# peripherals.net
KiCad netlist of a schematic drawn in Altium Designer
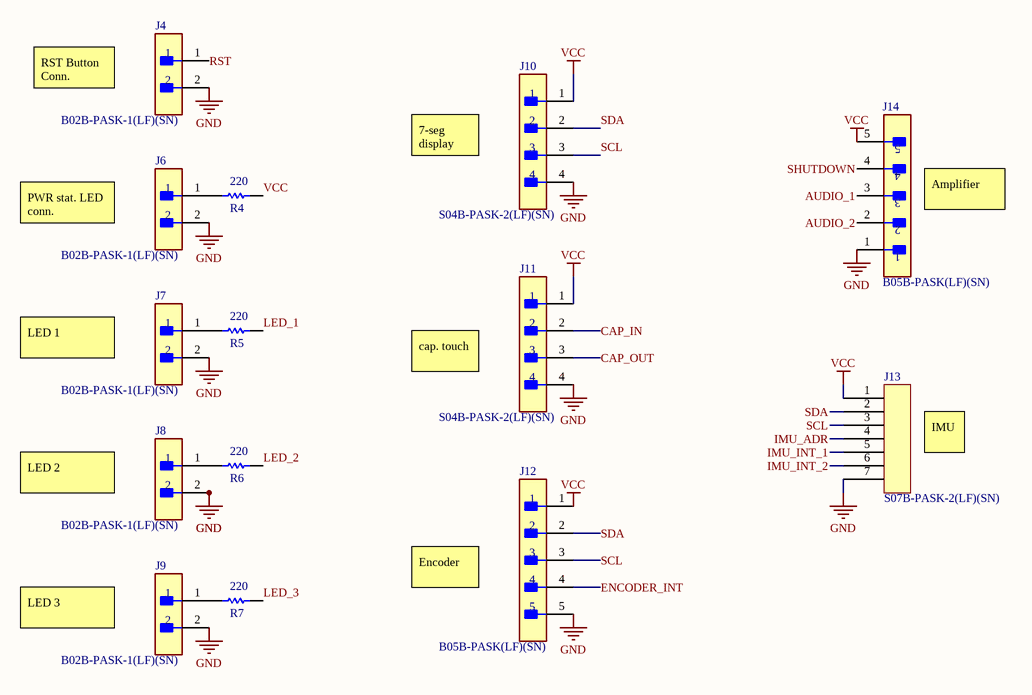
[diagram p0: peripherals.SchDoc]

(export (version "E")
  (design (tool "Eeschema 10.0.6"))
  (components
    (comp (ref "J4")
      (value "B02B-PASK-1(LF)(SN)")
      (footprint "FP-B02B-PASK-1_LF_SN-MFG")
      (description "CONN HEADER VERT 2POS 2MM")
      (libsource (lib "Altium Content Vault") (part "3bc925449376181038e59eaffc5286c"))
    )
    (comp (ref "J6")
      (value "B02B-PASK-1(LF)(SN)")
      (footprint "FP-B02B-PASK-1_LF_SN-MFG")
      (description "CONN HEADER VERT 2POS 2MM")
      (libsource (lib "Altium Content Vault") (part "3bc925449376181038e59eaffc5286c"))
    )
    (comp (ref "J7")
      (value "B02B-PASK-1(LF)(SN)")
      (footprint "FP-B02B-PASK-1_LF_SN-MFG")
      (description "CONN HEADER VERT 2POS 2MM")
      (libsource (lib "Altium Content Vault") (part "3bc925449376181038e59eaffc5286c"))
    )
    (comp (ref "J8")
      (value "B02B-PASK-1(LF)(SN)")
      (footprint "FP-B02B-PASK-1_LF_SN-MFG")
      (description "CONN HEADER VERT 2POS 2MM")
      (libsource (lib "Altium Content Vault") (part "3bc925449376181038e59eaffc5286c"))
    )
    (comp (ref "J9")
      (value "B02B-PASK-1(LF)(SN)")
      (footprint "FP-B02B-PASK-1_LF_SN-MFG")
      (description "CONN HEADER VERT 2POS 2MM")
      (libsource (lib "Altium Content Vault") (part "3bc925449376181038e59eaffc5286c"))
    )
    (comp (ref "J10")
      (value "S04B-PASK-2(LF)(SN)")
      (footprint "FP-S04B-PASK-2_LF_SN-MFG")
      (description "CONN HEADER R/A 4POS 2MM")
      (libsource (lib "Altium Content Vault") (part "299a8cea1bdcbc3624fe62c390fa72c"))
    )
    (comp (ref "J11")
      (value "S04B-PASK-2(LF)(SN)")
      (footprint "FP-S04B-PASK-2_LF_SN-MFG")
      (description "CONN HEADER R/A 4POS 2MM")
      (libsource (lib "Altium Content Vault") (part "299a8cea1bdcbc3624fe62c390fa72c"))
    )
    (comp (ref "J12")
      (value "B05B-PASK(LF)(SN)")
      (footprint "FP-B05B-PASK_LF_SN-MFG")
      (description "CONN HEADER VERT 5POS 2MM")
      (libsource (lib "Altium Content Vault") (part "bf93c07fd2649a848d0ec8585582aab"))
    )
    (comp (ref "J13")
      (value "S07B-PASK-2(LF)(SN)")
      (footprint "S07B-PASK-2(LF)(SN)-Footprint-1")
      (description "Conn Shrouded Header HDR 7 POS 2mm Solder RA Thru-Hole Box")
      (libsource (lib "University of Pittsburgh") (part "S07B-PASK-2(LF)(SN)-Symbol-1"))
    )
    (comp (ref "J14")
      (value "B05B-PASK(LF)(SN)")
      (footprint "FP-B05B-PASK_LF_SN-MFG")
      (description "CONN HEADER VERT 5POS 2MM")
      (libsource (lib "") (part "bf93c07fd2649a848d0ec8585582aab_1"))
    )
    (comp (ref "R4")
      (value "220")
      (footprint "RESA60-630X240")
      (description "RES 1K OHM 1/4W 1% AXIAL")
      (fields (field (name "TOLERANCE") "1%"))
      (libsource (lib "University of Pittsburgh") (part "RES-2"))
    )
    (comp (ref "R5")
      (value "220")
      (footprint "RESA60-630X240")
      (description "RES 1K OHM 1/4W 1% AXIAL")
      (fields (field (name "TOLERANCE") "1%"))
      (libsource (lib "University of Pittsburgh") (part "RES-2"))
    )
    (comp (ref "R6")
      (value "220")
      (footprint "RESA60-630X240")
      (description "RES 1K OHM 1/4W 1% AXIAL")
      (fields (field (name "TOLERANCE") "1%"))
      (libsource (lib "University of Pittsburgh") (part "RES-2"))
    )
    (comp (ref "R7")
      (value "220")
      (footprint "RESA60-630X240")
      (description "RES 1K OHM 1/4W 1% AXIAL")
      (fields (field (name "TOLERANCE") "1%"))
      (libsource (lib "University of Pittsburgh") (part "RES-2"))
    )
  )
  (nets
    (net (code "1") (name "/AUDIO_1") (class "Default")
      (node (ref "J14") (pin "3") (pinfunction "3_3") (pintype "passive"))
    )
    (net (code "2") (name "/AUDIO_2") (class "Default")
      (node (ref "J14") (pin "2") (pinfunction "2_2") (pintype "passive"))
    )
    (net (code "3") (name "/CAP_IN") (class "Default")
      (node (ref "J11") (pin "2") (pinfunction "2_2") (pintype "passive"))
    )
    (net (code "4") (name "/CAP_OUT") (class "Default")
      (node (ref "J11") (pin "3") (pinfunction "3_3") (pintype "passive"))
    )
    (net (code "5") (name "/ENCODER_INT") (class "Default")
      (node (ref "J12") (pin "4") (pinfunction "4_4") (pintype "passive"))
    )
    (net (code "6") (name "/IMU_ADR") (class "Default") (node (ref "J13") (pin "4") (pintype "passive")))
    (net (code "7") (name "/IMU_INT_1") (class "Default") (node (ref "J13") (pin "5") (pintype "passive")))
    (net (code "8") (name "/IMU_INT_2") (class "Default") (node (ref "J13") (pin "6") (pintype "passive")))
    (net (code "9") (name "/LED_1") (class "Default")
      (node (ref "R5") (pin "2") (pinfunction "2_2") (pintype "passive"))
    )
    (net (code "10") (name "/LED_2") (class "Default")
      (node (ref "R6") (pin "2") (pinfunction "2_2") (pintype "passive"))
    )
    (net (code "11") (name "/LED_3") (class "Default")
      (node (ref "R7") (pin "2") (pinfunction "2_2") (pintype "passive"))
    )
    (net (code "12") (name "/RST") (class "Default")
      (node (ref "J4") (pin "1") (pinfunction "1_1") (pintype "passive"))
    )
    (net (code "13") (name "/SCL") (class "Default")
      (node (ref "J10") (pin "3") (pinfunction "3_3") (pintype "passive"))
      (node (ref "J12") (pin "3") (pinfunction "3_3") (pintype "passive"))
      (node (ref "J13") (pin "3") (pintype "passive"))
    )
    (net (code "14") (name "/SDA") (class "Default")
      (node (ref "J10") (pin "2") (pinfunction "2_2") (pintype "passive"))
      (node (ref "J12") (pin "2") (pinfunction "2_2") (pintype "passive"))
      (node (ref "J13") (pin "2") (pintype "passive"))
    )
    (net (code "15") (name "/SHUTDOWN") (class "Default")
      (node (ref "J14") (pin "4") (pinfunction "4_4") (pintype "passive"))
    )
    (net (code "16") (name "GND") (class "Default")
      (node (ref "J10") (pin "4") (pinfunction "4_4") (pintype "passive"))
      (node (ref "J11") (pin "4") (pinfunction "4_4") (pintype "passive"))
      (node (ref "J12") (pin "5") (pinfunction "5_5") (pintype "passive"))
      (node (ref "J13") (pin "7") (pintype "passive"))
      (node (ref "J14") (pin "1") (pinfunction "1_1") (pintype "passive"))
      (node (ref "J4") (pin "2") (pinfunction "2_2") (pintype "passive"))
      (node (ref "J6") (pin "2") (pinfunction "2_2") (pintype "passive"))
      (node (ref "J7") (pin "2") (pinfunction "2_2") (pintype "passive"))
      (node (ref "J8") (pin "2") (pinfunction "2_2") (pintype "passive"))
      (node (ref "J9") (pin "2") (pinfunction "2_2") (pintype "passive"))
    )
    (net (code "17") (name "Net-(J6-Pad1)") (class "Default")
      (node (ref "J6") (pin "1") (pinfunction "1_1") (pintype "passive"))
      (node (ref "R4") (pin "1") (pinfunction "1_1") (pintype "passive"))
    )
    (net (code "18") (name "Net-(J7-Pad1)") (class "Default")
      (node (ref "J7") (pin "1") (pinfunction "1_1") (pintype "passive"))
      (node (ref "R5") (pin "1") (pinfunction "1_1") (pintype "passive"))
    )
    (net (code "19") (name "Net-(J8-Pad1)") (class "Default")
      (node (ref "J8") (pin "1") (pinfunction "1_1") (pintype "passive"))
      (node (ref "R6") (pin "1") (pinfunction "1_1") (pintype "passive"))
    )
    (net (code "20") (name "Net-(J9-Pad1)") (class "Default")
      (node (ref "J9") (pin "1") (pinfunction "1_1") (pintype "passive"))
      (node (ref "R7") (pin "1") (pinfunction "1_1") (pintype "passive"))
    )
    (net (code "21") (name "VCC") (class "Default")
      (node (ref "J10") (pin "1") (pinfunction "1_1") (pintype "passive"))
      (node (ref "J11") (pin "1") (pinfunction "1_1") (pintype "passive"))
      (node (ref "J12") (pin "1") (pinfunction "1_1") (pintype "passive"))
      (node (ref "J13") (pin "1") (pintype "passive"))
      (node (ref "J14") (pin "5") (pinfunction "5_5") (pintype "passive"))
      (node (ref "R4") (pin "2") (pinfunction "2_2") (pintype "passive"))
    )
  )
)
